# Power_Stage.net
KiCad netlist of a schematic drawn in Altium Designer
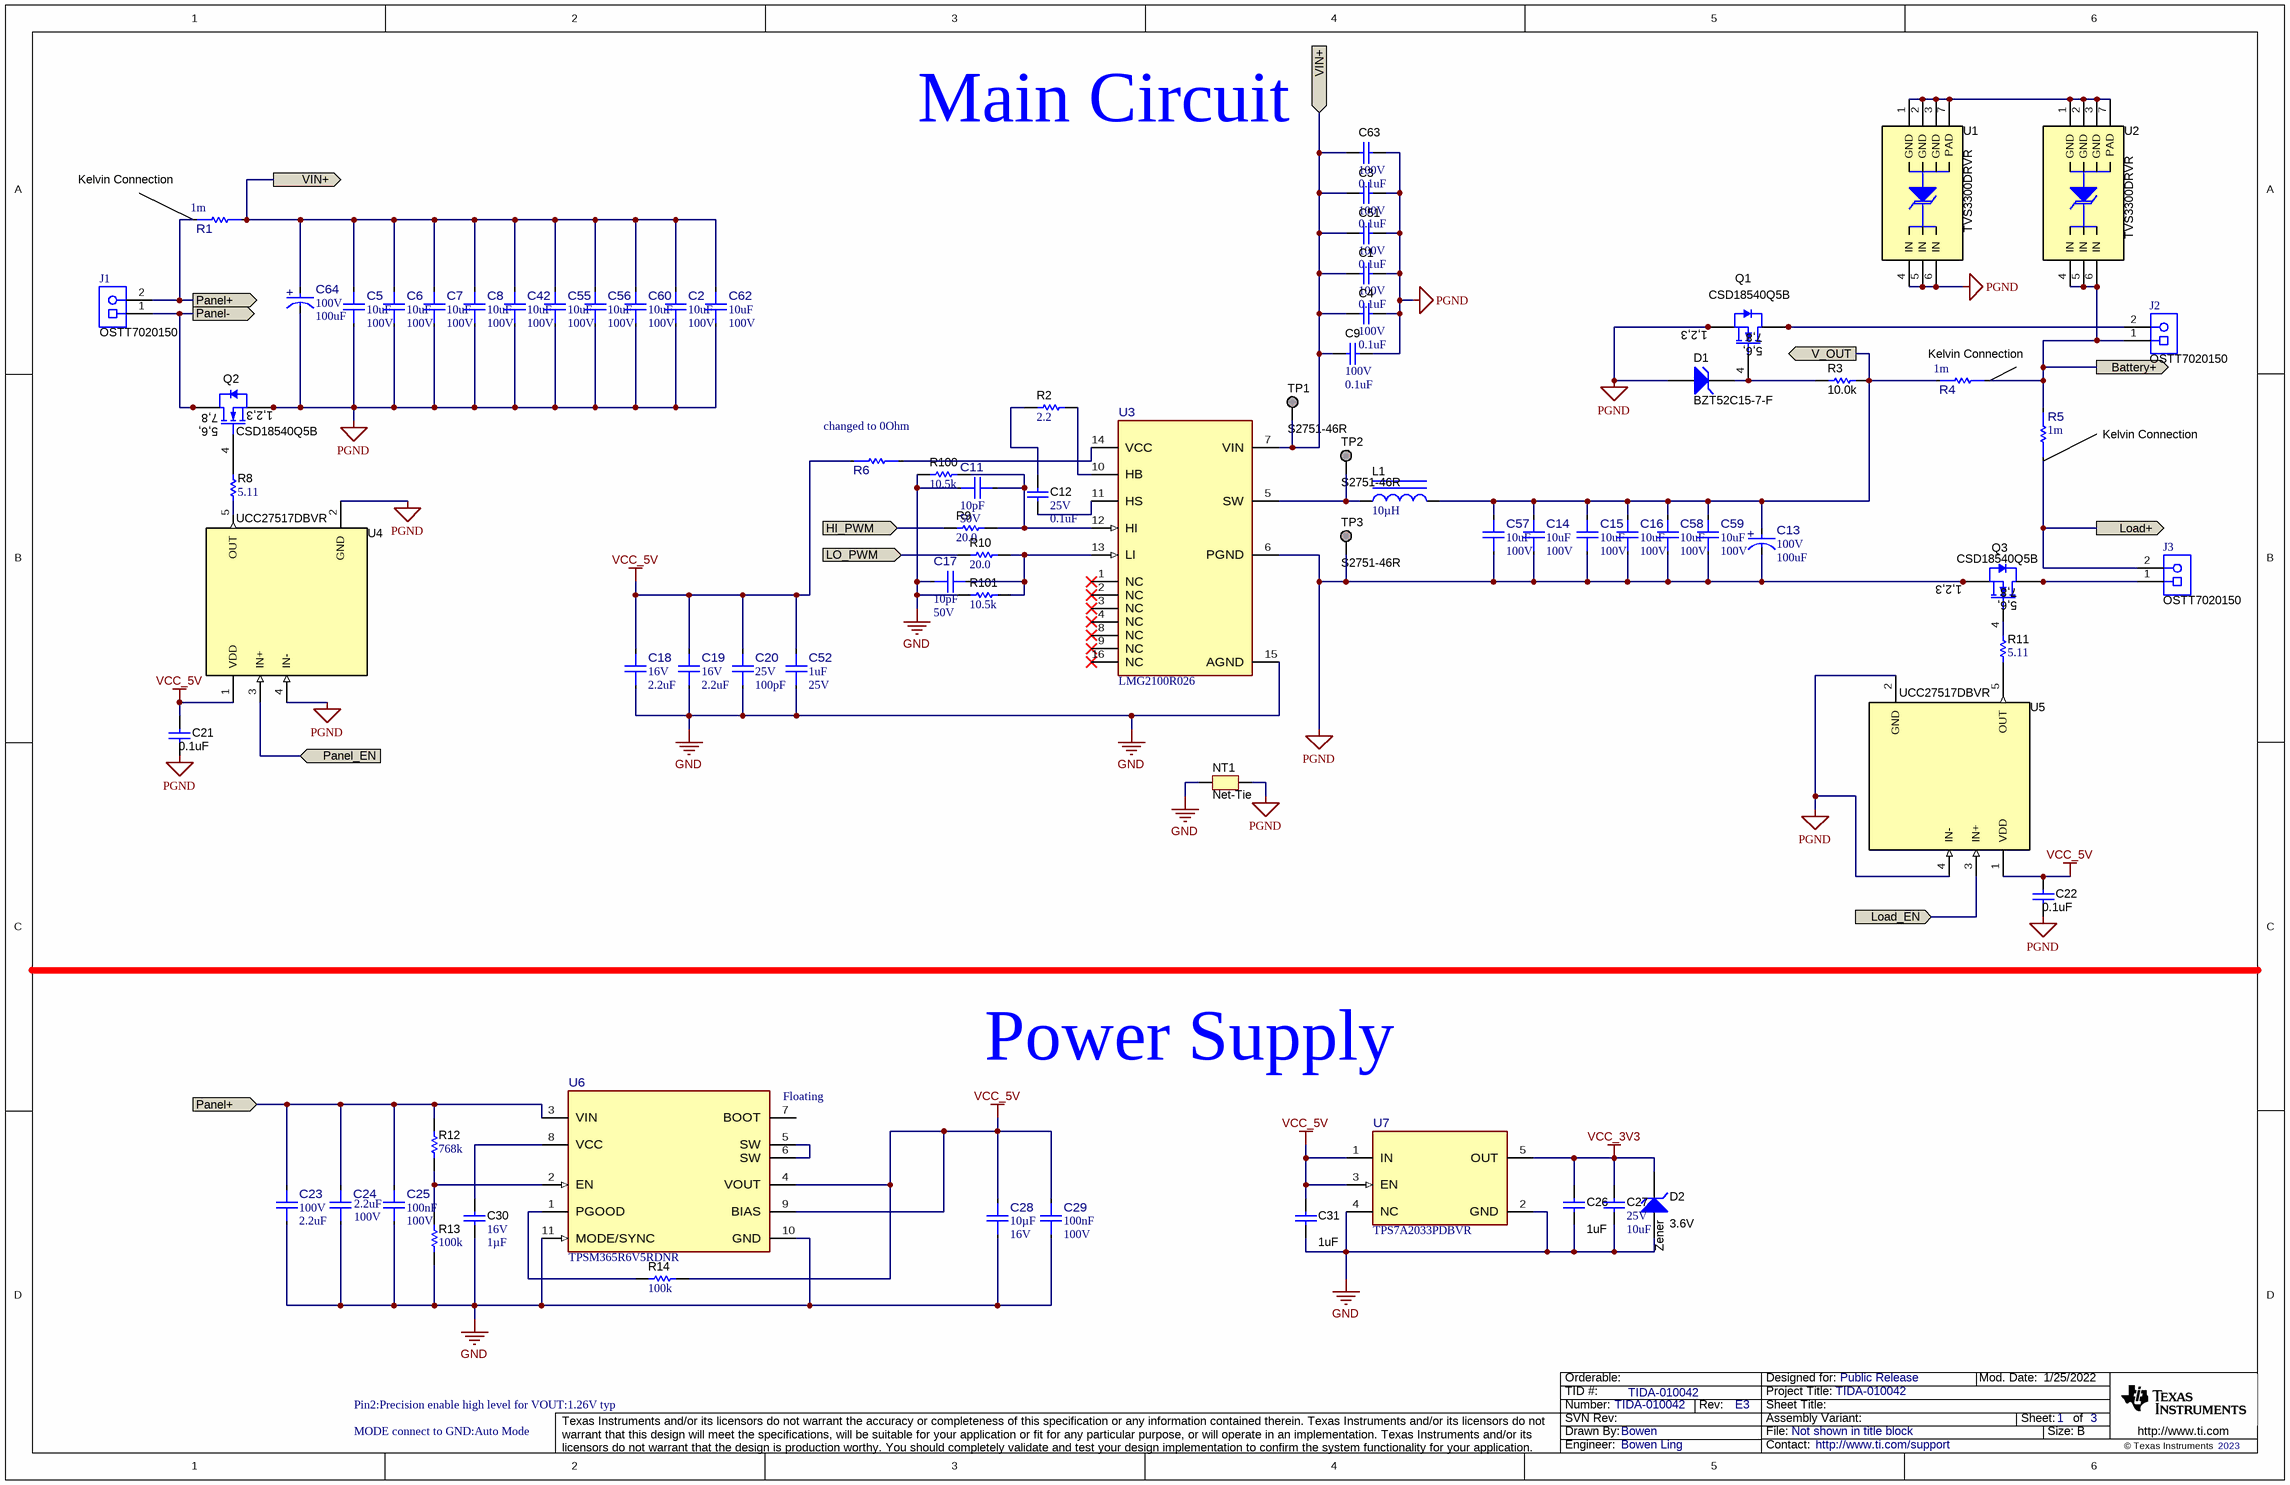
[diagram p0: Power Stage.SchDoc]

(export (version "E")
  (design (tool "Eeschema 10.0.6"))
  (components
    (comp (ref "C1")
      (value "GRM155R62A104KE14D")
      (footprint "0402S")
      (description "CAP, CERM, 0.1 uF, 100 V, +/- 10%, X5R, 0402")
      (fields
        (field (name "MANUFACTURER") "MuRata")
        (field (name "VDC_V") "100V")
        (field (name "VALUEDISPLAYED") "0.1uF")
        (field (name "PUBLISHER") "Texas Instruments")
      )
      (libsource (lib "Altium Vault - TI") (part "Capacitor"))
    )
    (comp (ref "C2")
      (value "GRM32EC72A106KE05L")
      (footprint "FP-GRM32EC72A106KE05L_1210-MFG")
      (description "10µF ±10% 100V Ceramic Capacitor X7S 1210 (3225 Metric)")
      (fields
        (field (name "VALUEDISPLAYED") "10uF")
        (field (name "MANUFACTURER") "Murata")
        (field (name "VDC_V") "100V")
      )
      (libsource (lib "Altium Vault - TI") (part "SYM-CC0402JRNPO9BN161"))
    )
    (comp (ref "C3")
      (value "GRM155R62A104KE14D")
      (footprint "0402S")
      (description "CAP, CERM, 0.1 uF, 100 V, +/- 10%, X5R, 0402")
      (fields
        (field (name "MANUFACTURER") "MuRata")
        (field (name "VDC_V") "100V")
        (field (name "VALUEDISPLAYED") "0.1uF")
        (field (name "PUBLISHER") "Texas Instruments")
      )
      (libsource (lib "Altium Vault - TI") (part "Capacitor"))
    )
    (comp (ref "C4")
      (value "GRM155R62A104KE14D")
      (footprint "0402S")
      (description "CAP, CERM, 0.1 uF, 100 V, +/- 10%, X5R, 0402")
      (fields
        (field (name "MANUFACTURER") "MuRata")
        (field (name "VDC_V") "100V")
        (field (name "VALUEDISPLAYED") "0.1uF")
        (field (name "PUBLISHER") "Texas Instruments")
      )
      (libsource (lib "Altium Vault - TI") (part "Capacitor"))
    )
    (comp (ref "C5")
      (value "GRM32EC72A106KE05L")
      (footprint "FP-GRM32EC72A106KE05L_1210-MFG")
      (description "10µF ±10% 100V Ceramic Capacitor X7S 1210 (3225 Metric)")
      (fields
        (field (name "VALUEDISPLAYED") "10uF")
        (field (name "MANUFACTURER") "Murata")
        (field (name "VDC_V") "100V")
      )
      (libsource (lib "Altium Vault - TI") (part "SYM-CC0402JRNPO9BN161"))
    )
    (comp (ref "C6")
      (value "GRM32EC72A106KE05L")
      (footprint "FP-GRM32EC72A106KE05L_1210-MFG")
      (description "10µF ±10% 100V Ceramic Capacitor X7S 1210 (3225 Metric)")
      (fields
        (field (name "VALUEDISPLAYED") "10uF")
        (field (name "MANUFACTURER") "Murata")
        (field (name "VDC_V") "100V")
      )
      (libsource (lib "Altium Vault - TI") (part "SYM-CC0402JRNPO9BN161"))
    )
    (comp (ref "C7")
      (value "GRM32EC72A106KE05L")
      (footprint "FP-GRM32EC72A106KE05L_1210-MFG")
      (description "10µF ±10% 100V Ceramic Capacitor X7S 1210 (3225 Metric)")
      (fields
        (field (name "VALUEDISPLAYED") "10uF")
        (field (name "MANUFACTURER") "Murata")
        (field (name "VDC_V") "100V")
      )
      (libsource (lib "Altium Vault - TI") (part "SYM-CC0402JRNPO9BN161"))
    )
    (comp (ref "C8")
      (value "GRM32EC72A106KE05L")
      (footprint "FP-GRM32EC72A106KE05L_1210-MFG")
      (description "10µF ±10% 100V Ceramic Capacitor X7S 1210 (3225 Metric)")
      (fields
        (field (name "VALUEDISPLAYED") "10uF")
        (field (name "MANUFACTURER") "Murata")
        (field (name "VDC_V") "100V")
      )
      (libsource (lib "Altium Vault - TI") (part "SYM-CC0402JRNPO9BN161"))
    )
    (comp (ref "C9")
      (value "GRM155R62A104KE14D")
      (footprint "0402S")
      (description "CAP, CERM, 0.1 uF, 100 V, +/- 10%, X5R, 0402")
      (fields
        (field (name "MANUFACTURER") "MuRata")
        (field (name "VDC_V") "100V")
        (field (name "VALUEDISPLAYED") "0.1uF")
        (field (name "PUBLISHER") "Texas Instruments")
      )
      (libsource (lib "Altium Vault - TI") (part "Capacitor"))
    )
    (comp (ref "C11")
      (value "04025U100FAT2A")
      (footprint "FP-04025U100FAT2A_0402-MFG")
      (description "10 pF ±1% 50V Ceramic Capacitor C0G, NP0 0402 (1005 Metric)")
      (fields
        (field (name "MANUFACTURER") "KYOCERA AVX")
        (field (name "VALUEDISPLAYED") "10pF")
        (field (name "DIGIKEY PART NUMBER") "478-5717-1-ND")
        (field (name "VDC_V") "50V")
      )
      (libsource (lib "Altium Vault - TI") (part "SYM-04025U100FAT2A"))
    )
    (comp (ref "C12")
      (value "GRM155R71E104KE14D")
      (footprint "0402S")
      (description "CAP, CERM, 0.1 uF, 25 V, +/- 10%, X7R, 0402")
      (fields
        (field (name "MANUFACTURER") "MuRata")
        (field (name "VDC_V") "25V")
        (field (name "VALUEDISPLAYED") "0.1uF")
        (field (name "PUBLISHER") "Texas Instruments")
      )
      (libsource (lib "Altium Vault - TI") (part "Capacitor"))
    )
    (comp (ref "C13")
      (value "ESY107M100AH5")
      (footprint "FP-ESY476M100AH1AA_RADIAL-MFG")
      (description "100 µF 100 V Aluminum Electrolytic Capacitors Radial, Can 180mOhm @ 100kHz 4000 Hrs @ 105°C")
      (fields
        (field (name "PART NUMBER") "ESY476M100AH1AA")
        (field (name "MANUFACTURER") "Kemet")
        (field (name "VDC_V") "100V")
        (field (name "VALUEDISPLAYED") "100uF")
      )
      (libsource (lib "Altium Vault - TI") (part "SYM-ESY476M100AH1AA"))
    )
    (comp (ref "C14")
      (value "GRM32EC72A106KE05L")
      (footprint "FP-GRM32EC72A106KE05L_1210-MFG")
      (description "10µF ±10% 100V Ceramic Capacitor X7S 1210 (3225 Metric)")
      (fields
        (field (name "VALUEDISPLAYED") "10uF")
        (field (name "MANUFACTURER") "Murata")
        (field (name "VDC_V") "100V")
      )
      (libsource (lib "Altium Vault - TI") (part "SYM-CC0402JRNPO9BN161"))
    )
    (comp (ref "C15")
      (value "GRM32EC72A106KE05L")
      (footprint "FP-GRM32EC72A106KE05L_1210-MFG")
      (description "10µF ±10% 100V Ceramic Capacitor X7S 1210 (3225 Metric)")
      (fields
        (field (name "VALUEDISPLAYED") "10uF")
        (field (name "MANUFACTURER") "Murata")
        (field (name "VDC_V") "100V")
      )
      (libsource (lib "Altium Vault - TI") (part "SYM-CC0402JRNPO9BN161"))
    )
    (comp (ref "C16")
      (value "GRM32EC72A106KE05L")
      (footprint "FP-GRM32EC72A106KE05L_1210-MFG")
      (description "10µF ±10% 100V Ceramic Capacitor X7S 1210 (3225 Metric)")
      (fields
        (field (name "VALUEDISPLAYED") "10uF")
        (field (name "MANUFACTURER") "Murata")
        (field (name "VDC_V") "100V")
      )
      (libsource (lib "Altium Vault - TI") (part "SYM-CC0402JRNPO9BN161"))
    )
    (comp (ref "C17")
      (value "04025U100FAT2A")
      (footprint "FP-04025U100FAT2A_0402-MFG")
      (description "10 pF ±1% 50V Ceramic Capacitor C0G, NP0 0402 (1005 Metric)")
      (fields
        (field (name "MANUFACTURER") "KYOCERA AVX")
        (field (name "VALUEDISPLAYED") "10pF")
        (field (name "DIGIKEY PART NUMBER") "478-5717-1-ND")
        (field (name "VDC_V") "50V")
      )
      (libsource (lib "Altium Vault - TI") (part "SYM-04025U100FAT2A"))
    )
    (comp (ref "C18")
      (value "GRM188C71C225KE11D")
      (footprint "FP-GRM188C71C225KE11D_0603-MFG")
      (description "2.2µF ±10% 16V Ceramic Capacitor X7S 0603 (1608 Metric)")
      (fields
        (field (name "MANUFACTURER") "Murata")
        (field (name "VDC_V") "16V")
        (field (name "DIGIKEY PART NUMBER") "490-12731-1-ND")
        (field (name "VALUEDISPLAYED") "2.2uF")
      )
      (libsource (lib "Altium Vault - TI") (part "SYM-GRM188C71C225KE11D"))
    )
    (comp (ref "C19")
      (value "GRM188C71C225KE11D")
      (footprint "FP-GRM188C71C225KE11D_0603-MFG")
      (description "2.2µF ±10% 16V Ceramic Capacitor X7S 0603 (1608 Metric)")
      (fields
        (field (name "MANUFACTURER") "Murata")
        (field (name "VDC_V") "16V")
        (field (name "DIGIKEY PART NUMBER") "490-12731-1-ND")
        (field (name "VALUEDISPLAYED") "2.2uF")
      )
      (libsource (lib "Altium Vault - TI") (part "SYM-GRM188C71C225KE11D"))
    )
    (comp (ref "C20")
      (value "GRT1555C1E101JA02D")
      (footprint "FP-GRT1555C1E101JA02D_0402-MFG")
      (description "Multi-Layer Ceramic Capacitor 100pF 25V C0G ±5% 0402 Paper T/R")
      (fields
        (field (name "VDC_V") "25V")
        (field (name "VALUEDISPLAYED") "100pF")
        (field (name "MANUFACTURER") "Murata")
      )
      (libsource (lib "Altium Vault - TI") (part "SYM-GRT1555C1E101JA02D"))
    )
    (comp (ref "C21")
      (value "GMK107BJ104KAHT")
      (footprint "0603")
      (description "CAP CER 0.1UF 25V X5R 0603")
      (fields
        (field (name "MANUFACTURER") "Taiyo Yuden")
        (field (name "PARTNUMBER") "TMK107BJ104KA-T")
        (field (name "VALUEDISPLAYED") "0.1uF")
        (field (name "PUBLISHER") "Texas Instruments")
      )
      (libsource (lib "Altium Vault - TI") (part "CMP-0007044-5"))
    )
    (comp (ref "C22")
      (value "GMK107BJ104KAHT")
      (footprint "0603")
      (description "CAP CER 0.1UF 25V X5R 0603")
      (fields
        (field (name "MANUFACTURER") "Taiyo Yuden")
        (field (name "PARTNUMBER") "TMK107BJ104KA-T")
        (field (name "VALUEDISPLAYED") "0.1uF")
        (field (name "PUBLISHER") "Texas Instruments")
      )
      (libsource (lib "Altium Vault - TI") (part "CMP-0007044-5"))
    )
    (comp (ref "C23")
      (value "12061C225KAT2A")
      (footprint "FP-12061C225KAT2A_1206-MFG")
      (description "2.2uF @ ±10% 100V Ceramic Capacitor X7R 15% 1206 (3216 Metric)")
      (fields
        (field (name "VDC_V") "100V")
        (field (name "DIGIKEY PART NUMBER") "478-10860-1-ND")
        (field (name "MOUSER PART NUMBER") "581-12061C225KAT2A")
        (field (name "VALUEDISPLAYED") "2.2uF")
      )
      (libsource (lib "Altium Vault - TI") (part "SYM-12061C225KAT2A"))
    )
    (comp (ref "C24")
      (value "12061C225KAT2A")
      (footprint "FP-12061C225KAT2A_1206-MFG")
      (description "2.2uF @ ±10% 100V Ceramic Capacitor X7R 15% 1206 (3216 Metric)")
      (fields
        (field (name "VDC_V") "100V")
        (field (name "DIGIKEY PART NUMBER") "478-10860-1-ND")
        (field (name "MOUSER PART NUMBER") "581-12061C225KAT2A")
        (field (name "VALUEDISPLAYED") "2.2uF")
      )
      (libsource (lib "Altium Vault - TI") (part "SYM-12061C225KAT2A"))
    )
    (comp (ref "C25")
      (value "GRM188R72A104KA35D")
      (footprint "FP-GRM188R72A104KA35D_0603-MFG")
      (description "0.1µF ±10% 100V Ceramic Capacitor X7R 0603 (1608 Metric)")
      (fields
        (field (name "CAP_F") "100nF")
        (field (name "VDC_V") "100V")
        (field (name "DIGIKEY PART NUMBER") "490-3285-1-ND")
        (field (name "MANUFACTURER") "Murata")
      )
      (libsource (lib "Altium Vault - TI") (part "SYM-GRM188R72A104KA35D"))
    )
    (comp (ref "C26")
      (value "C1608X7R1E105K080AB")
      (footprint "0603")
      (description "CAP CER 1UF 16V Y5V 0603")
      (fields
        (field (name "MANUFACTURER") "Yageo")
        (field (name "PARTNUMBER") "CC0603MRY5V7BB105")
        (field (name "VALUEDISPLAYED") "1uF")
        (field (name "PUBLISHER") "Texas Instruments")
      )
      (libsource (lib "Altium Vault - TI") (part "CMP-0006831-4"))
    )
    (comp (ref "C27")
      (value "GRM31CR71E106KA12L")
      (footprint "1206_180")
      (description "CAP, CERM, 10 uF, 25 V, +/- 10%, X7R, 1206")
      (fields
        (field (name "MANUFACTURER") "MuRata")
        (field (name "VDC_V") "25V")
        (field (name "VALUEDISPLAYED") "10uF")
        (field (name "PUBLISHER") "Texas Instruments")
      )
      (libsource (lib "Altium Vault - TI") (part "Capacitor"))
    )
    (comp (ref "C28")
      (value "CL21B106KOQNNNG")
      (footprint "FP-CL21B106KOQNNNG_0805-MFG")
      (description "Cap Ceramic 10uF 16V X7R 10% Pad SMD 0805 125°C T/R")
      (fields
        (field (name "CAP_F") "10µF")
        (field (name "VDC_V") "16V")
        (field (name "MANUFACTURER") "Samsung Electro-Mechanics")
        (field (name "DIGIKEY PART NUMBER") "1276-6472-1-ND")
      )
      (libsource (lib "Altium Vault - TI") (part "SYM-CL21B106KOQNNNG"))
    )
    (comp (ref "C29")
      (value "GRM188R72A104KA35D")
      (footprint "FP-GRM188R72A104KA35D_0603-MFG")
      (description "0.1µF ±10% 100V Ceramic Capacitor X7R 0603 (1608 Metric)")
      (fields
        (field (name "CAP_F") "100nF")
        (field (name "VDC_V") "100V")
        (field (name "DIGIKEY PART NUMBER") "490-3285-1-ND")
        (field (name "MANUFACTURER") "Murata")
      )
      (libsource (lib "Altium Vault - TI") (part "SYM-GRM188R72A104KA35D"))
    )
    (comp (ref "C30")
      (value "CL10B105KO8VPNC")
      (footprint "0603")
      (description "CAP, CERM, 1 µF, 16 V,+/- 10%, X7R, AEC-Q200 Grade 1, 0603")
      (fields
        (field (name "VDC_V") "16V")
        (field (name "MANUFACTURER") "Samsung Electro-Mechanics")
        (field (name "CAP_F") "1µF")
      )
      (libsource (lib "Altium Vault - TI") (part "Capacitor"))
    )
    (comp (ref "C31")
      (value "C1608X7R1E105K080AB")
      (footprint "0603")
      (description "CAP CER 1UF 16V Y5V 0603")
      (fields
        (field (name "MANUFACTURER") "Yageo")
        (field (name "PARTNUMBER") "CC0603MRY5V7BB105")
        (field (name "VALUEDISPLAYED") "1uF")
        (field (name "PUBLISHER") "Texas Instruments")
      )
      (libsource (lib "Altium Vault - TI") (part "CMP-0006831-4"))
    )
    (comp (ref "C42")
      (value "GRM32EC72A106KE05L")
      (footprint "FP-GRM32EC72A106KE05L_1210-MFG")
      (description "10µF ±10% 100V Ceramic Capacitor X7S 1210 (3225 Metric)")
      (fields
        (field (name "VALUEDISPLAYED") "10uF")
        (field (name "MANUFACTURER") "Murata")
        (field (name "VDC_V") "100V")
      )
      (libsource (lib "Altium Vault - TI") (part "SYM-CC0402JRNPO9BN161"))
    )
    (comp (ref "C51")
      (value "GRM155R62A104KE14D")
      (footprint "0402S")
      (description "CAP, CERM, 0.1 uF, 100 V, +/- 10%, X5R, 0402")
      (fields
        (field (name "MANUFACTURER") "MuRata")
        (field (name "VDC_V") "100V")
        (field (name "VALUEDISPLAYED") "0.1uF")
        (field (name "PUBLISHER") "Texas Instruments")
      )
      (libsource (lib "Altium Vault - TI") (part "Capacitor"))
    )
    (comp (ref "C52")
      (value "GRT155R61E105KE01D")
      (footprint "FP-GRT155R61E105KE01D_0402-MFG")
      (description "Multi-Layer Ceramic Capacitor 1uF 25V X5R ±10% 0402 Paper T/R")
      (fields
        (field (name "MANUFACTURER") "Murata")
        (field (name "VALUEDISPLAYED") "1uF")
        (field (name "VDC_V") "25V")
      )
      (libsource (lib "Altium Vault - TI") (part "SYM-GRT155R61E105KE01D"))
    )
    (comp (ref "C55")
      (value "GRM32EC72A106KE05L")
      (footprint "FP-GRM32EC72A106KE05L_1210-MFG")
      (description "10µF ±10% 100V Ceramic Capacitor X7S 1210 (3225 Metric)")
      (fields
        (field (name "VALUEDISPLAYED") "10uF")
        (field (name "MANUFACTURER") "Murata")
        (field (name "VDC_V") "100V")
      )
      (libsource (lib "Altium Vault - TI") (part "SYM-CC0402JRNPO9BN161"))
    )
    (comp (ref "C56")
      (value "GRM32EC72A106KE05L")
      (footprint "FP-GRM32EC72A106KE05L_1210-MFG")
      (description "10µF ±10% 100V Ceramic Capacitor X7S 1210 (3225 Metric)")
      (fields
        (field (name "VALUEDISPLAYED") "10uF")
        (field (name "MANUFACTURER") "Murata")
        (field (name "VDC_V") "100V")
      )
      (libsource (lib "Altium Vault - TI") (part "SYM-CC0402JRNPO9BN161"))
    )
    (comp (ref "C57")
      (value "GRM32EC72A106KE05L")
      (footprint "FP-GRM32EC72A106KE05L_1210-MFG")
      (description "10µF ±10% 100V Ceramic Capacitor X7S 1210 (3225 Metric)")
      (fields
        (field (name "VALUEDISPLAYED") "10uF")
        (field (name "MANUFACTURER") "Murata")
        (field (name "VDC_V") "100V")
      )
      (libsource (lib "Altium Vault - TI") (part "SYM-CC0402JRNPO9BN161"))
    )
    (comp (ref "C58")
      (value "GRM32EC72A106KE05L")
      (footprint "FP-GRM32EC72A106KE05L_1210-MFG")
      (description "10µF ±10% 100V Ceramic Capacitor X7S 1210 (3225 Metric)")
      (fields
        (field (name "VALUEDISPLAYED") "10uF")
        (field (name "MANUFACTURER") "Murata")
        (field (name "VDC_V") "100V")
      )
      (libsource (lib "Altium Vault - TI") (part "SYM-CC0402JRNPO9BN161"))
    )
    (comp (ref "C59")
      (value "GRM32EC72A106KE05L")
      (footprint "FP-GRM32EC72A106KE05L_1210-MFG")
      (description "10µF ±10% 100V Ceramic Capacitor X7S 1210 (3225 Metric)")
      (fields
        (field (name "VALUEDISPLAYED") "10uF")
        (field (name "MANUFACTURER") "Murata")
        (field (name "VDC_V") "100V")
      )
      (libsource (lib "Altium Vault - TI") (part "SYM-CC0402JRNPO9BN161"))
    )
    (comp (ref "C60")
      (value "GRM32EC72A106KE05L")
      (footprint "FP-GRM32EC72A106KE05L_1210-MFG")
      (description "10µF ±10% 100V Ceramic Capacitor X7S 1210 (3225 Metric)")
      (fields
        (field (name "VALUEDISPLAYED") "10uF")
        (field (name "MANUFACTURER") "Murata")
        (field (name "VDC_V") "100V")
      )
      (libsource (lib "Altium Vault - TI") (part "SYM-CC0402JRNPO9BN161"))
    )
    (comp (ref "C62")
      (value "GRM32EC72A106KE05L")
      (footprint "FP-GRM32EC72A106KE05L_1210-MFG")
      (description "10µF ±10% 100V Ceramic Capacitor X7S 1210 (3225 Metric)")
      (fields
        (field (name "VALUEDISPLAYED") "10uF")
        (field (name "MANUFACTURER") "Murata")
        (field (name "VDC_V") "100V")
      )
      (libsource (lib "Altium Vault - TI") (part "SYM-CC0402JRNPO9BN161"))
    )
    (comp (ref "C63")
      (value "GRM155R62A104KE14D")
      (footprint "0402S")
      (description "CAP, CERM, 0.1 uF, 100 V, +/- 10%, X5R, 0402")
      (fields
        (field (name "MANUFACTURER") "MuRata")
        (field (name "VDC_V") "100V")
        (field (name "VALUEDISPLAYED") "0.1uF")
        (field (name "PUBLISHER") "Texas Instruments")
      )
      (libsource (lib "Altium Vault - TI") (part "Capacitor"))
    )
    (comp (ref "C64")
      (value "ESY107M100AH5")
      (footprint "FP-ESY476M100AH1AA_RADIAL-MFG")
      (description "100 µF 100 V Aluminum Electrolytic Capacitors Radial, Can 180mOhm @ 100kHz 4000 Hrs @ 105°C")
      (fields
        (field (name "PART NUMBER") "ESY476M100AH1AA")
        (field (name "MANUFACTURER") "Kemet")
        (field (name "VDC_V") "100V")
        (field (name "VALUEDISPLAYED") "100uF")
      )
      (libsource (lib "Altium Vault - TI") (part "SYM-ESY476M100AH1AA"))
    )
    (comp (ref "D1")
      (value "BZT52C15-7-F")
      (footprint "SOD-123")
      (description "Diode, Zener, 15 V, 370 mW, AEC-Q101, SOD-123")
      (fields (field (name "MANUFACTURER") "Diodes Inc.") (field (name "PUBLISHER") "Texas Instruments"))
      (libsource (lib "Altium Vault - TI") (part "Zener"))
    )
    (comp (ref "D2")
      (value "Zener")
      (footprint "SOD-123")
      (description "Diode, Zener, 3.6 V, 500 mW, SOD-123")
      (fields
        (field (name "ALTIUM_VALUE") "3.6V")
        (field (name "PARTNUMBER") "MMSZ4685T1G")
        (field (name "MANUFACTURER") "ON Semiconductor")
        (field (name "PUBLISHER") "Texas Instruments")
      )
      (libsource (lib "Altium Vault - TI") (part "Zener"))
    )
    (comp (ref "J1")
      (value "OSTT7020150")
      (footprint "On-Shore_OSTT7020150")
      (description "Terminal Block, 6.35mm, 2x1, TH")
      (fields
        (field (name "MANUFACTURER") "On-Shore Technology")
        (field (name "PUBLISHER") "Texas Instruments")
      )
      (libsource (lib "Altium Vault - TI") (part "Receptacle_2x1"))
    )
    (comp (ref "J2")
      (value "OSTT7020150")
      (footprint "On-Shore_OSTT7020150")
      (description "Terminal Block, 6.35mm, 2x1, TH")
      (fields
        (field (name "MANUFACTURER") "On-Shore Technology")
        (field (name "PUBLISHER") "Texas Instruments")
      )
      (libsource (lib "") (part "Receptacle_2x1_1"))
    )
    (comp (ref "J3")
      (value "OSTT7020150")
      (footprint "On-Shore_OSTT7020150")
      (description "Terminal Block, 6.35mm, 2x1, TH")
      (fields
        (field (name "MANUFACTURER") "On-Shore Technology")
        (field (name "PUBLISHER") "Texas Instruments")
      )
      (libsource (lib "") (part "Receptacle_2x1_1"))
    )
    (comp (ref "L1")
      (value "7443641000")
      (footprint "WE-HCF_2818")
      (description "Inductor, Shielded, Ferrite, 10 µH, 30 A, 0.0024 ohm, SMD")
      (fields (field (name "MANUFACTURER") "Wurth Elektronik") (field (name "VALUEDISPLAYED") "10µH"))
      (libsource (lib "Altium Vault - TI") (part "Inductor_Iron"))
    )
    (comp (ref "NT1")
      (value "Net-Tie")
      (footprint "Net-Tie_0805_HV_NoOverlay")
      (description "Single point connection between nets.")
      (libsource (lib "Altium Vault - TI") (part "Net-Tie"))
    )
    (comp (ref "Q1")
      (value "CSD18540Q5B")
      (footprint "DNK0008A")
      (description "MOSFET, N-CH, 60 V, 100 A, DNK0008A (VSON-CLIP-8)")
      (fields (field (name "MANUFACTURER") "Texas Instruments"))
      (libsource (lib "Altium Vault - TI") (part "MOSFET_N_D56789G4S123"))
    )
    (comp (ref "Q2")
      (value "CSD18540Q5B")
      (footprint "DNK0008A")
      (description "MOSFET, N-CH, 60 V, 100 A, DNK0008A (VSON-CLIP-8)")
      (fields (field (name "MANUFACTURER") "Texas Instruments"))
      (libsource (lib "Altium Vault - TI") (part "MOSFET_N_D56789G4S123"))
    )
    (comp (ref "Q3")
      (value "CSD18540Q5B")
      (footprint "DNK0008A")
      (description "MOSFET, N-CH, 60 V, 100 A, DNK0008A (VSON-CLIP-8)")
      (fields (field (name "MANUFACTURER") "Texas Instruments"))
      (libsource (lib "Altium Vault - TI") (part "MOSFET_N_D56789G4S123"))
    )
    (comp (ref "R1")
      (value "1m")
      (footprint "FP-ULRG32512R001FLFSLT_2512-MFG")
      (description "Res Metal Strip 2512 0.001 Ohm 1% 3W ±50ppm/C Pad SMD Automotive T/R")
      (fields
        (field (name "MANUFACTURER") "TT Electronics")
        (field (name "PARTNUMBER") "ULRG32512R001FLFSLT")
      )
      (libsource (lib "Altium Vault - TI") (part "SYM-ULRG32512R001FLFSLT"))
    )
    (comp (ref "R2")
      (value "CRCW04022R20JNED")
      (footprint "0402S")
      (description "RES, 2.2, 5%, 0.063 W, AEC-Q200 Grade 0, 0402")
      (fields (field (name "MANUFACTURER") "Vishay-Dale") (field (name "VALUEDISPLAYED") "2.2"))
      (libsource (lib "Altium Vault - TI") (part "Resistor"))
    )
    (comp (ref "R3")
      (value "Resistor")
      (footprint "0603")
      (description "RES, 10.0 k, 0.1%, 0.1 W, 0603")
      (fields
        (field (name "PARTNUMBER") "RG1608P-103-B-T5")
        (field (name "VALUEDISPLAYED") "10.0k")
        (field (name "MANUFACTURER") "Susumu Co Ltd")
        (field (name "PUBLISHER") "Texas Instruments")
      )
      (libsource (lib "Altium Vault - TI") (part "Resistor"))
    )
    (comp (ref "R4")
      (value "1m")
      (footprint "FP-ULRG32512R001FLFSLT_2512-MFG")
      (description "Res Metal Strip 2512 0.001 Ohm 1% 3W ±50ppm/C Pad SMD Automotive T/R")
      (fields
        (field (name "MANUFACTURER") "TT Electronics")
        (field (name "PARTNUMBER") "ULRG32512R001FLFSLT")
      )
      (libsource (lib "Altium Vault - TI") (part "SYM-ULRG32512R001FLFSLT"))
    )
    (comp (ref "R5")
      (value "1m")
      (footprint "FP-ULRG32512R001FLFSLT_2512-MFG")
      (description "Res Metal Strip 2512 0.001 Ohm 1% 3W ±50ppm/C Pad SMD Automotive T/R")
      (fields
        (field (name "MANUFACTURER") "TT Electronics")
        (field (name "PARTNUMBER") "ULRG32512R001FLFSLT")
      )
      (libsource (lib "Altium Vault - TI") (part "SYM-ULRG32512R001FLFSLT"))
    )
    (comp (ref "R6")
      (value "RCG04020000Z0ED")
      (footprint "FP-RCG04020000Z0ED_0402-MFG")
      (description "Res Thick Film 0402 0 Ohm 1/16W Molded SMD")
      (fields
        (field (name "MOUSER PART NUMBER") "71-RCG04020000Z0ED")
        (field (name "DIGIKEY PART NUMBER") "541-1887-1-ND")
      )
      (libsource (lib "Altium Vault - TI") (part "SYM-RCG04020000Z0ED"))
    )
    (comp (ref "R8")
      (value "5.11")
      (footprint "1206")
      (description "RES, 5.11, 1%, 0.25 W, AEC-Q200 Grade 0, 1206")
      (fields (field (name "MANUFACTURER") "Vishay-Dale") (field (name "PARTNUMBER") "CRCW12065R11FKEA"))
      (libsource (lib "Altium Vault - TI") (part "CMP-0017092-3"))
    )
    (comp (ref "R9")
      (value "RC0603FR-0720RL")
      (footprint "0603")
      (description "RES, 20.0, 1%, 0.1 W, 0603")
      (fields (field (name "MANUFACTURER") "Yageo") (field (name "VALUEDISPLAYED") "20.0"))
      (libsource (lib "Altium Vault - TI") (part "Resistor"))
    )
    (comp (ref "R10")
      (value "RC0603FR-0720RL")
      (footprint "0603")
      (description "RES, 20.0, 1%, 0.1 W, 0603")
      (fields (field (name "MANUFACTURER") "Yageo") (field (name "VALUEDISPLAYED") "20.0"))
      (libsource (lib "Altium Vault - TI") (part "Resistor"))
    )
    (comp (ref "R11")
      (value "5.11")
      (footprint "1206")
      (description "RES, 5.11, 1%, 0.25 W, AEC-Q200 Grade 0, 1206")
      (fields (field (name "MANUFACTURER") "Vishay-Dale") (field (name "PARTNUMBER") "CRCW12065R11FKEA"))
      (libsource (lib "Altium Vault - TI") (part "CMP-0017092-3"))
    )
    (comp (ref "R12")
      (value "RC0603FR-07768KL")
      (footprint "0603")
      (description "RES, 768 k, 1%, 0.1 W, 0603")
      (fields (field (name "MANUFACTURER") "Yageo") (field (name "VALUEDISPLAYED") "768k"))
      (libsource (lib "Altium Vault - TI") (part "Resistor"))
    )
    (comp (ref "R13")
      (value "RC0603FR-07100KL")
      (footprint "0603")
      (description "RES, 100 k, 1%, 0.1 W, 0603")
      (fields (field (name "MANUFACTURER") "Yageo") (field (name "VALUEDISPLAYED") "100k"))
      (libsource (lib "Altium Vault - TI") (part "Resistor"))
    )
    (comp (ref "R14")
      (value "RC0402FR-07100KL")
      (footprint "0402")
      (description "RES, 100 k, 1%, 0.0625 W, 0402")
      (fields
        (field (name "MANUFACTURER") "Yageo America")
        (field (name "VALUEDISPLAYED") "100k")
        (field (name "PUBLISHER") "Texas Instruments")
      )
      (libsource (lib "Altium Vault - TI") (part "Resistor"))
    )
    (comp (ref "R100")
      (value "RC0402FR-0710K5L")
      (footprint "0402S")
      (description "RES, 10.5 k, 1%, 0.063 W, 0402")
      (fields (field (name "MANUFACTURER") "Yageo America") (field (name "VALUEDISPLAYED") "10.5k"))
      (libsource (lib "Altium Vault - TI") (part "Resistor"))
    )
    (comp (ref "R101")
      (value "RC0402FR-0710K5L")
      (footprint "0402S")
      (description "RES, 10.5 k, 1%, 0.063 W, 0402")
      (fields (field (name "MANUFACTURER") "Yageo America") (field (name "VALUEDISPLAYED") "10.5k"))
      (libsource (lib "Altium Vault - TI") (part "Resistor"))
    )
    (comp (ref "TP1")
      (value "S2751-46R")
      (footprint "Harwin_S2751-46R")
      (description "Test Point, SMT")
      (fields (field (name "MANUFACTURER") "Harwin") (field (name "PUBLISHER") "Texas Instruments"))
      (libsource (lib "Altium Vault - TI") (part "TESTPOINT"))
    )
    (comp (ref "TP2")
      (value "S2751-46R")
      (footprint "Harwin_S2751-46R")
      (description "Test Point, SMT")
      (fields (field (name "MANUFACTURER") "Harwin") (field (name "PUBLISHER") "Texas Instruments"))
      (libsource (lib "Altium Vault - TI") (part "TESTPOINT"))
    )
    (comp (ref "TP3")
      (value "S2751-46R")
      (footprint "Harwin_S2751-46R")
      (description "Test Point, SMT")
      (fields (field (name "MANUFACTURER") "Harwin") (field (name "PUBLISHER") "Texas Instruments"))
      (libsource (lib "Altium Vault - TI") (part "TESTPOINT"))
    )
    (comp (ref "U1")
      (value "TVS3300DRVR")
      (footprint "DRV0006A")
      (description "33-V Precision Surge Protection Clamp, DRV0006A (WSON-6)")
      (fields
        (field (name "PARTNUMBER") "TVS3300DRVR")
        (field (name "MANUFACTURER") "Texas Instruments")
        (field (name "ALTERNATE PARTNUMBER") "TVS3300DRVT")
      )
      (libsource (lib "Altium Vault - TI") (part "CMP-0013424-7"))
    )
    (comp (ref "U2")
      (value "TVS3300DRVR")
      (footprint "DRV0006A")
      (description "33-V Precision Surge Protection Clamp, DRV0006A (WSON-6)")
      (fields
        (field (name "PARTNUMBER") "TVS3300DRVR")
        (field (name "MANUFACTURER") "Texas Instruments")
        (field (name "ALTERNATE PARTNUMBER") "TVS3300DRVT")
      )
      (libsource (lib "Altium Vault - TI") (part "CMP-0013424-7"))
    )
    (comp (ref "U3")
      (value "LMG2100R026")
      (footprint "VBN0016A-MFG")
      (description "100-V, 53-A GaN Half-Bridge Power Stage")
      (fields (field (name "MANUFACTURER") "Texas Instruments") (field (name "PARTNUMBER") "LMG2100R026"))
      (libsource (lib "Altium Vault - TI") (part "SYM-LMG2100R026"))
    )
    (comp (ref "U4")
      (value "UCC27517DBVR")
      (footprint "DBV0005A_N")
      (description "4A/4A Single Channel High-speed Low-side Gate Driver, DBV0005A (SOT-23-5)")
      (fields
        (field (name "ALTERNATE PARTNUMBER") "UCC27517DBVT")
        (field (name "MANUFACTURER") "Texas Instruments")
        (field (name "PARTNUMBER") "UCC27517DBVR")
        (field (name "PUBLISHER") "Texas Instruments")
      )
      (libsource (lib "") (part "CMP-0066947-1_1"))
    )
    (comp (ref "U5")
      (value "UCC27517DBVR")
      (footprint "DBV0005A_N")
      (description "4A/4A Single Channel High-speed Low-side Gate Driver, DBV0005A (SOT-23-5)")
      (fields
        (field (name "ALTERNATE PARTNUMBER") "UCC27517DBVT")
        (field (name "MANUFACTURER") "Texas Instruments")
        (field (name "PARTNUMBER") "UCC27517DBVR")
        (field (name "PUBLISHER") "Texas Instruments")
      )
      (libsource (lib "Altium Vault - TI") (part "CMP-0066947-1"))
    )
    (comp (ref "U6")
      (value "TPSM365R6V5RDNR")
      (footprint "RDN0011A-MFG")
      (fields (field (name "MANUFACTURER") "Texas Instruments") (field (name "PARTNUMBER") "TPSM365R6V5RDNR"))
      (libsource (lib "Altium Vault - TI") (part "SYM-TPSM365R6V5RDNR"))
    )
    (comp (ref "U7")
      (value "TPS7A2033PDBVR")
      (footprint "DBV0005A-MFG")
      (description "300-mA, Ultra-Low-Noise, Low-IQ, High PSRR LDO")
      (fields
        (field (name "MANUFACTURER") "Texas Instruments")
        (field (name "DIGIKEY PART NUMBER") "296-TPS7A2033PDBVRCT-ND")
        (field (name "PARTNUMBER") "TPS7A2033PDBVR")
      )
      (libsource (lib "Altium Vault - TI") (part "SYM-TPS7A2033PDBVR"))
    )
  )
  (nets
    (net (code "1") (name "/Battery+") (class "Default")
      (node (ref "J2") (pin "1") (pinfunction "1_1") (pintype "passive"))
      (node (ref "R4") (pin "2") (pinfunction "2_2") (pintype "passive"))
      (node (ref "R5") (pin "2") (pinfunction "2_2") (pintype "passive"))
      (node (ref "U2") (pin "4") (pinfunction "IN_4") (pintype "passive"))
      (node (ref "U2") (pin "5") (pinfunction "IN_5") (pintype "passive"))
      (node (ref "U2") (pin "6") (pinfunction "IN_6") (pintype "passive"))
    )
    (net (code "2") (name "/HI_PWM") (class "Default")
      (node (ref "R9") (pin "1") (pinfunction "1_1") (pintype "passive"))
    )
    (net (code "3") (name "/LO_PWM") (class "Default")
      (node (ref "R10") (pin "1") (pinfunction "1_1") (pintype "passive"))
    )
    (net (code "4") (name "/Load+") (class "Default")
      (node (ref "J3") (pin "2") (pinfunction "2_2") (pintype "passive"))
      (node (ref "R5") (pin "1") (pinfunction "1_1") (pintype "passive"))
    )
    (net (code "5") (name "/Load_EN") (class "Default")
      (node (ref "U5") (pin "3") (pinfunction "IN+_3") (pintype "input"))
    )
    (net (code "6") (name "/Panel+") (class "Default")
      (node (ref "C23") (pin "2") (pinfunction "2_2") (pintype "passive"))
      (node (ref "C24") (pin "2") (pinfunction "2_2") (pintype "passive"))
      (node (ref "C25") (pin "2") (pinfunction "2_2") (pintype "passive"))
      (node (ref "J1") (pin "2") (pinfunction "2_2") (pintype "passive"))
      (node (ref "R1") (pin "1") (pinfunction "1_1") (pintype "passive"))
      (node (ref "R12") (pin "2") (pinfunction "2_2") (pintype "passive"))
      (node (ref "U6") (pin "3") (pinfunction "VIN_3") (pintype "power_in"))
    )
    (net (code "7") (name "/Panel-") (class "Default")
      (node (ref "J1") (pin "1") (pinfunction "1_1") (pintype "passive"))
      (node (ref "Q2") (pin "5") (pinfunction "D_5") (pintype "passive"))
      (node (ref "Q2") (pin "6") (pinfunction "D_6") (pintype "passive"))
      (node (ref "Q2") (pin "7") (pinfunction "D_7") (pintype "passive"))
      (node (ref "Q2") (pin "8") (pinfunction "D_8") (pintype "passive"))
      (node (ref "Q2") (pin "9") (pinfunction "D_9") (pintype "passive"))
    )
    (net (code "8") (name "/Panel_EN") (class "Default")
      (node (ref "U4") (pin "3") (pinfunction "IN+_3") (pintype "input"))
    )
    (net (code "9") (name "/VIN+") (class "Default")
      (node (ref "C1") (pin "2") (pinfunction "2_2") (pintype "passive"))
      (node (ref "C2") (pin "2") (pinfunction "2_2") (pintype "passive"))
      (node (ref "C3") (pin "2") (pinfunction "2_2") (pintype "passive"))
      (node (ref "C4") (pin "2") (pinfunction "2_2") (pintype "passive"))
      (node (ref "C42") (pin "2") (pinfunction "2_2") (pintype "passive"))
      (node (ref "C5") (pin "2") (pinfunction "2_2") (pintype "passive"))
      (node (ref "C51") (pin "2") (pinfunction "2_2") (pintype "passive"))
      (node (ref "C55") (pin "2") (pinfunction "2_2") (pintype "passive"))
      (node (ref "C56") (pin "2") (pinfunction "2_2") (pintype "passive"))
      (node (ref "C6") (pin "2") (pinfunction "2_2") (pintype "passive"))
      (node (ref "C60") (pin "2") (pinfunction "2_2") (pintype "passive"))
      (node (ref "C62") (pin "2") (pinfunction "2_2") (pintype "passive"))
      (node (ref "C63") (pin "2") (pinfunction "2_2") (pintype "passive"))
      (node (ref "C64") (pin "2") (pinfunction "ANODE_2") (pintype "passive"))
      (node (ref "C7") (pin "2") (pinfunction "2_2") (pintype "passive"))
      (node (ref "C8") (pin "2") (pinfunction "2_2") (pintype "passive"))
      (node (ref "C9") (pin "2") (pinfunction "2_2") (pintype "passive"))
      (node (ref "R1") (pin "2") (pinfunction "2_2") (pintype "passive"))
      (node (ref "TP1") (pin "1") (pintype "passive"))
      (node (ref "U3") (pin "7") (pinfunction "VIN_7") (pintype "power_in"))
    )
    (net (code "10") (name "/V_OUT") (class "Default")
      (node (ref "C13") (pin "2") (pinfunction "ANODE_2") (pintype "passive"))
      (node (ref "C14") (pin "2") (pinfunction "2_2") (pintype "passive"))
      (node (ref "C15") (pin "2") (pinfunction "2_2") (pintype "passive"))
      (node (ref "C16") (pin "2") (pinfunction "2_2") (pintype "passive"))
      (node (ref "C57") (pin "2") (pinfunction "2_2") (pintype "passive"))
      (node (ref "C58") (pin "2") (pinfunction "2_2") (pintype "passive"))
      (node (ref "C59") (pin "2") (pinfunction "2_2") (pintype "passive"))
      (node (ref "L1") (pin "2") (pinfunction "2_2") (pintype "passive"))
      (node (ref "R3") (pin "2") (pinfunction "2_2") (pintype "passive"))
      (node (ref "R4") (pin "1") (pinfunction "1_1") (pintype "passive"))
    )
    (net (code "11") (name "GND") (class "Default")
      (node (ref "C11") (pin "1") (pinfunction "1_1") (pintype "passive"))
      (node (ref "C17") (pin "1") (pinfunction "1_1") (pintype "passive"))
      (node (ref "C18") (pin "1") (pinfunction "1_1") (pintype "passive"))
      (node (ref "C19") (pin "1") (pinfunction "1_1") (pintype "passive"))
      (node (ref "C20") (pin "1") (pinfunction "1_1") (pintype "passive"))
      (node (ref "C23") (pin "1") (pinfunction "1_1") (pintype "passive"))
      (node (ref "C24") (pin "1") (pinfunction "1_1") (pintype "passive"))
      (node (ref "C25") (pin "1") (pinfunction "1_1") (pintype "passive"))
      (node (ref "C26") (pin "2") (pinfunction "2_2") (pintype "passive"))
      (node (ref "C27") (pin "2") (pinfunction "2_2") (pintype "passive"))
      (node (ref "C28") (pin "1") (pinfunction "1_1") (pintype "passive"))
      (node (ref "C29") (pin "1") (pinfunction "1_1") (pintype "passive"))
      (node (ref "C30") (pin "2") (pinfunction "2_2") (pintype "passive"))
      (node (ref "C31") (pin "2") (pinfunction "2_2") (pintype "passive"))
      (node (ref "C52") (pin "1") (pinfunction "1_1") (pintype "passive"))
      (node (ref "D2") (pin "2") (pinfunction "A_2") (pintype "passive"))
      (node (ref "NT1") (pin "1") (pinfunction "1_1") (pintype "passive"))
      (node (ref "R100") (pin "2") (pinfunction "2_2") (pintype "passive"))
      (node (ref "R101") (pin "2") (pinfunction "2_2") (pintype "passive"))
      (node (ref "R13") (pin "1") (pinfunction "1_1") (pintype "passive"))
      (node (ref "U3") (pin "15") (pinfunction "AGND_15") (pintype "power_in"))
      (node (ref "U6") (pin "10") (pinfunction "GND_10") (pintype "power_in"))
      (node (ref "U6") (pin "11") (pinfunction "MODE/SYNC_11") (pintype "input"))
      (node (ref "U7") (pin "2") (pinfunction "GND_2") (pintype "power_in"))
      (node (ref "U7") (pin "4") (pinfunction "NC_4") (pintype "passive"))
    )
    (net (code "12") (name "Net-(C12-Pad1)") (class "Default")
      (node (ref "C12") (pin "1") (pinfunction "1_1") (pintype "passive"))
      (node (ref "R2") (pin "1") (pinfunction "1_1") (pintype "passive"))
    )
    (net (code "13") (name "Net-(D1-K)") (class "Default")
      (node (ref "D1") (pin "1") (pinfunction "K_1") (pintype "passive"))
      (node (ref "Q1") (pin "4") (pinfunction "G_4") (pintype "passive"))
      (node (ref "R3") (pin "1") (pinfunction "1_1") (pintype "passive"))
    )
    (net (code "14") (name "Net-(J2-Pad2)") (class "Default")
      (node (ref "J2") (pin "2") (pinfunction "2_2") (pintype "passive"))
      (node (ref "Q1") (pin "5") (pinfunction "D_5") (pintype "passive"))
      (node (ref "Q1") (pin "6") (pinfunction "D_6") (pintype "passive"))
      (node (ref "Q1") (pin "7") (pinfunction "D_7") (pintype "passive"))
      (node (ref "Q1") (pin "8") (pinfunction "D_8") (pintype "passive"))
      (node (ref "Q1") (pin "9") (pinfunction "D_9") (pintype "passive"))
    )
    (net (code "15") (name "Net-(J3-Pad1)") (class "Default")
      (node (ref "J3") (pin "1") (pinfunction "1_1") (pintype "passive"))
      (node (ref "Q3") (pin "5") (pinfunction "D_5") (pintype "passive"))
      (node (ref "Q3") (pin "6") (pinfunction "D_6") (pintype "passive"))
      (node (ref "Q3") (pin "7") (pinfunction "D_7") (pintype "passive"))
      (node (ref "Q3") (pin "8") (pinfunction "D_8") (pintype "passive"))
      (node (ref "Q3") (pin "9") (pinfunction "D_9") (pintype "passive"))
    )
    (net (code "16") (name "Net-(Q2-G)") (class "Default")
      (node (ref "Q2") (pin "4") (pinfunction "G_4") (pintype "passive"))
      (node (ref "R8") (pin "2") (pinfunction "2_2") (pintype "passive"))
    )
    (net (code "17") (name "Net-(Q3-G)") (class "Default")
      (node (ref "Q3") (pin "4") (pinfunction "G_4") (pintype "passive"))
      (node (ref "R11") (pin "2") (pinfunction "2_2") (pintype "passive"))
    )
    (net (code "18") (name "Net-(U1-PAD)") (class "Default")
      (node (ref "U1") (pin "1") (pinfunction "GND_1") (pintype "passive"))
      (node (ref "U1") (pin "2") (pinfunction "GND_2") (pintype "passive"))
      (node (ref "U1") (pin "3") (pinfunction "GND_3") (pintype "passive"))
      (node (ref "U1") (pin "7") (pinfunction "PAD_7") (pintype "passive"))
      (node (ref "U2") (pin "1") (pinfunction "GND_1") (pintype "passive"))
      (node (ref "U2") (pin "2") (pinfunction "GND_2") (pintype "passive"))
      (node (ref "U2") (pin "3") (pinfunction "GND_3") (pintype "passive"))
      (node (ref "U2") (pin "7") (pinfunction "PAD_7") (pintype "passive"))
    )
    (net (code "19") (name "Net-(U3-HB)") (class "Default")
      (node (ref "R2") (pin "2") (pinfunction "2_2") (pintype "passive"))
      (node (ref "U3") (pin "10") (pinfunction "HB_10") (pintype "power_in"))
    )
    (net (code "20") (name "Net-(U3-HI)") (class "Default")
      (node (ref "C11") (pin "2") (pinfunction "2_2") (pintype "passive"))
      (node (ref "R100") (pin "1") (pinfunction "1_1") (pintype "passive"))
      (node (ref "R9") (pin "2") (pinfunction "2_2") (pintype "passive"))
      (node (ref "U3") (pin "12") (pinfunction "HI_12") (pintype "input"))
    )
    (net (code "21") (name "Net-(U3-HS)") (class "Default")
      (node (ref "C12") (pin "2") (pinfunction "2_2") (pintype "passive"))
      (node (ref "U3") (pin "11") (pinfunction "HS_11") (pintype "power_in"))
    )
    (net (code "22") (name "Net-(U3-LI)") (class "Default")
      (node (ref "C17") (pin "2") (pinfunction "2_2") (pintype "passive"))
      (node (ref "R10") (pin "2") (pinfunction "2_2") (pintype "passive"))
      (node (ref "R101") (pin "1") (pinfunction "1_1") (pintype "passive"))
      (node (ref "U3") (pin "13") (pinfunction "LI_13") (pintype "input"))
    )
    (net (code "23") (name "Net-(U3-SW)") (class "Default")
      (node (ref "L1") (pin "1") (pinfunction "1_1") (pintype "passive"))
      (node (ref "TP2") (pin "1") (pintype "passive"))
      (node (ref "U3") (pin "5") (pinfunction "SW_5") (pintype "power_in"))
    )
    (net (code "24") (name "Net-(U3-VCC)") (class "Default")
      (node (ref "R6") (pin "2") (pinfunction "2_2") (pintype "passive"))
      (node (ref "U3") (pin "14") (pinfunction "VCC_14") (pintype "power_in"))
    )
    (net (code "25") (name "Net-(U4-OUT)") (class "Default")
      (node (ref "R8") (pin "1") (pinfunction "1_1") (pintype "passive"))
      (node (ref "U4") (pin "5") (pinfunction "OUT_5") (pintype "output"))
    )
    (net (code "26") (name "Net-(U5-OUT)") (class "Default")
      (node (ref "R11") (pin "1") (pinfunction "1_1") (pintype "passive"))
      (node (ref "U5") (pin "5") (pinfunction "OUT_5") (pintype "output"))
    )
    (net (code "27") (name "Net-(U6-EN)") (class "Default")
      (node (ref "R12") (pin "1") (pinfunction "1_1") (pintype "passive"))
      (node (ref "R13") (pin "2") (pinfunction "2_2") (pintype "passive"))
      (node (ref "U6") (pin "2") (pinfunction "EN_2") (pintype "input"))
    )
    (net (code "28") (name "Net-(U6-PGOOD)") (class "Default")
      (node (ref "R14") (pin "1") (pinfunction "1_1") (pintype "passive"))
      (node (ref "U6") (pin "1") (pinfunction "PGOOD_1") (pintype "open_collector"))
    )
    (net (code "29") (name "Net-(U6-SW-Pad5)") (class "Default")
      (node (ref "U6") (pin "5") (pinfunction "SW_5") (pintype "power_in"))
      (node (ref "U6") (pin "6") (pinfunction "SW_6") (pintype "power_in"))
    )
    (net (code "30") (name "Net-(U6-VCC)") (class "Default")
      (node (ref "C30") (pin "1") (pinfunction "1_1") (pintype "passive"))
      (node (ref "U6") (pin "8") (pinfunction "VCC_8") (pintype "power_in"))
    )
    (net (code "31") (name "PGND") (class "Default")
      (node (ref "C1") (pin "1") (pinfunction "1_1") (pintype "passive"))
      (node (ref "C13") (pin "1") (pinfunction "CATHODE_1") (pintype "passive"))
      (node (ref "C14") (pin "1") (pinfunction "1_1") (pintype "passive"))
      (node (ref "C15") (pin "1") (pinfunction "1_1") (pintype "passive"))
      (node (ref "C16") (pin "1") (pinfunction "1_1") (pintype "passive"))
      (node (ref "C2") (pin "1") (pinfunction "1_1") (pintype "passive"))
      (node (ref "C21") (pin "2") (pinfunction "2_2") (pintype "passive"))
      (node (ref "C22") (pin "2") (pinfunction "2_2") (pintype "passive"))
      (node (ref "C3") (pin "1") (pinfunction "1_1") (pintype "passive"))
      (node (ref "C4") (pin "1") (pinfunction "1_1") (pintype "passive"))
      (node (ref "C42") (pin "1") (pinfunction "1_1") (pintype "passive"))
      (node (ref "C5") (pin "1") (pinfunction "1_1") (pintype "passive"))
      (node (ref "C51") (pin "1") (pinfunction "1_1") (pintype "passive"))
      (node (ref "C55") (pin "1") (pinfunction "1_1") (pintype "passive"))
      (node (ref "C56") (pin "1") (pinfunction "1_1") (pintype "passive"))
      (node (ref "C57") (pin "1") (pinfunction "1_1") (pintype "passive"))
      (node (ref "C58") (pin "1") (pinfunction "1_1") (pintype "passive"))
      (node (ref "C59") (pin "1") (pinfunction "1_1") (pintype "passive"))
      (node (ref "C6") (pin "1") (pinfunction "1_1") (pintype "passive"))
      (node (ref "C60") (pin "1") (pinfunction "1_1") (pintype "passive"))
      (node (ref "C62") (pin "1") (pinfunction "1_1") (pintype "passive"))
      (node (ref "C63") (pin "1") (pinfunction "1_1") (pintype "passive"))
      (node (ref "C64") (pin "1") (pinfunction "CATHODE_1") (pintype "passive"))
      (node (ref "C7") (pin "1") (pinfunction "1_1") (pintype "passive"))
      (node (ref "C8") (pin "1") (pinfunction "1_1") (pintype "passive"))
      (node (ref "C9") (pin "1") (pinfunction "1_1") (pintype "passive"))
      (node (ref "D1") (pin "2") (pinfunction "A_2") (pintype "passive"))
      (node (ref "NT1") (pin "2") (pinfunction "2_2") (pintype "passive"))
      (node (ref "Q1") (pin "1") (pinfunction "S_1") (pintype "passive"))
      (node (ref "Q1") (pin "2") (pinfunction "S_2") (pintype "passive"))
      (node (ref "Q1") (pin "3") (pinfunction "S_3") (pintype "passive"))
      (node (ref "Q2") (pin "1") (pinfunction "S_1") (pintype "passive"))
      (node (ref "Q2") (pin "2") (pinfunction "S_2") (pintype "passive"))
      (node (ref "Q2") (pin "3") (pinfunction "S_3") (pintype "passive"))
      (node (ref "Q3") (pin "1") (pinfunction "S_1") (pintype "passive"))
      (node (ref "Q3") (pin "2") (pinfunction "S_2") (pintype "passive"))
      (node (ref "Q3") (pin "3") (pinfunction "S_3") (pintype "passive"))
      (node (ref "TP3") (pin "1") (pintype "passive"))
      (node (ref "U1") (pin "4") (pinfunction "IN_4") (pintype "passive"))
      (node (ref "U1") (pin "5") (pinfunction "IN_5") (pintype "passive"))
      (node (ref "U1") (pin "6") (pinfunction "IN_6") (pintype "passive"))
      (node (ref "U3") (pin "6") (pinfunction "PGND_6") (pintype "power_in"))
      (node (ref "U4") (pin "2") (pinfunction "GND_2") (pintype "power_in"))
      (node (ref "U4") (pin "4") (pinfunction "IN-_4") (pintype "input"))
      (node (ref "U5") (pin "2") (pinfunction "GND_2") (pintype "power_in"))
      (node (ref "U5") (pin "4") (pinfunction "IN-_4") (pintype "input"))
    )
    (net (code "32") (name "VCC_3V3") (class "Default")
      (node (ref "C26") (pin "1") (pinfunction "1_1") (pintype "passive"))
      (node (ref "C27") (pin "1") (pinfunction "1_1") (pintype "passive"))
      (node (ref "D2") (pin "1") (pinfunction "K_1") (pintype "passive"))
      (node (ref "U7") (pin "5") (pinfunction "OUT_5") (pintype "passive"))
    )
    (net (code "33") (name "VCC_5V") (class "Default")
      (node (ref "C18") (pin "2") (pinfunction "2_2") (pintype "passive"))
      (node (ref "C19") (pin "2") (pinfunction "2_2") (pintype "passive"))
      (node (ref "C20") (pin "2") (pinfunction "2_2") (pintype "passive"))
      (node (ref "C21") (pin "1") (pinfunction "1_1") (pintype "passive"))
      (node (ref "C22") (pin "1") (pinfunction "1_1") (pintype "passive"))
      (node (ref "C28") (pin "2") (pinfunction "2_2") (pintype "passive"))
      (node (ref "C29") (pin "2") (pinfunction "2_2") (pintype "passive"))
      (node (ref "C31") (pin "1") (pinfunction "1_1") (pintype "passive"))
      (node (ref "C52") (pin "2") (pinfunction "2_2") (pintype "passive"))
      (node (ref "R14") (pin "2") (pinfunction "2_2") (pintype "passive"))
      (node (ref "R6") (pin "1") (pinfunction "1_1") (pintype "passive"))
      (node (ref "U4") (pin "1") (pinfunction "VDD_1") (pintype "power_in"))
      (node (ref "U5") (pin "1") (pinfunction "VDD_1") (pintype "power_in"))
      (node (ref "U6") (pin "4") (pinfunction "VOUT_4") (pintype "power_in"))
      (node (ref "U6") (pin "9") (pinfunction "BIAS_9") (pintype "passive"))
      (node (ref "U7") (pin "1") (pinfunction "IN_1") (pintype "power_in"))
      (node (ref "U7") (pin "3") (pinfunction "EN_3") (pintype "input"))
    )
    (net (code "34") (name "unconnected-(U3-NC-Pad1)") (class "Default")
      (node (ref "U3") (pin "1") (pinfunction "NC_1") (pintype "passive+no_connect"))
    )
    (net (code "35") (name "unconnected-(U3-NC-Pad2)") (class "Default")
      (node (ref "U3") (pin "2") (pinfunction "NC_2") (pintype "passive+no_connect"))
    )
    (net (code "36") (name "unconnected-(U3-NC-Pad3)") (class "Default")
      (node (ref "U3") (pin "3") (pinfunction "NC_3") (pintype "passive+no_connect"))
    )
    (net (code "37") (name "unconnected-(U3-NC-Pad4)") (class "Default")
      (node (ref "U3") (pin "4") (pinfunction "NC_4") (pintype "passive+no_connect"))
    )
    (net (code "38") (name "unconnected-(U3-NC-Pad8)") (class "Default")
      (node (ref "U3") (pin "8") (pinfunction "NC_8") (pintype "passive+no_connect"))
    )
    (net (code "39") (name "unconnected-(U3-NC-Pad9)") (class "Default")
      (node (ref "U3") (pin "9") (pinfunction "NC_9") (pintype "passive+no_connect"))
    )
    (net (code "40") (name "unconnected-(U3-NC-Pad16)") (class "Default")
      (node (ref "U3") (pin "16") (pinfunction "NC_16") (pintype "passive+no_connect"))
    )
    (net (code "41") (name "unconnected-(U6-BOOT-Pad7)") (class "Default")
      (node (ref "U6") (pin "7") (pinfunction "BOOT_7") (pintype "power_in"))
    )
  )
)
